# mapleSDuino-V0_1_016-eagle7.net
KiCad netlist of a schematic drawn in EAGLE
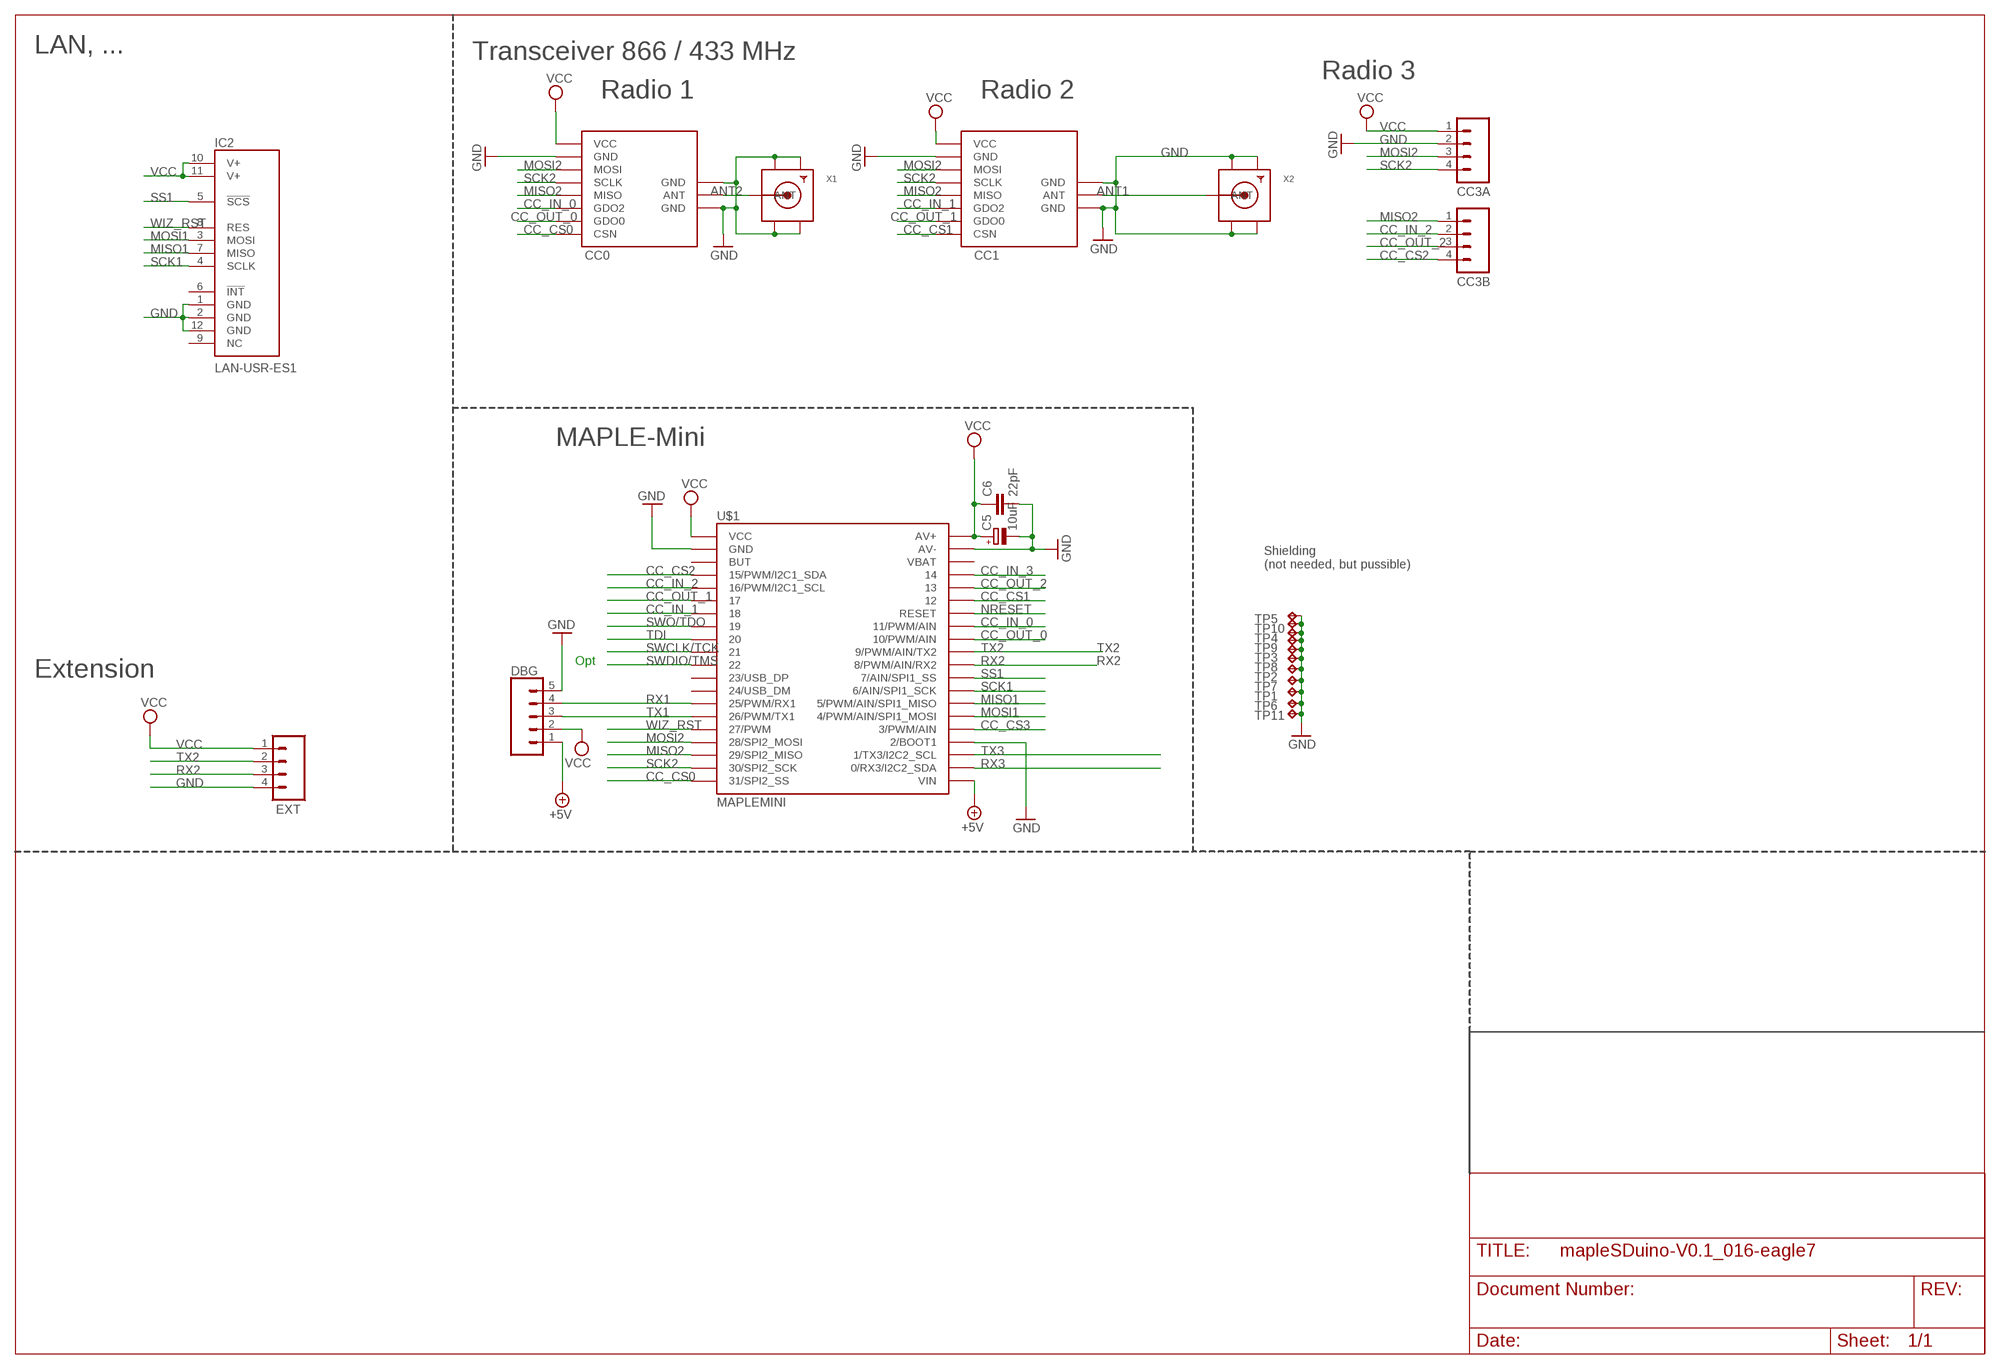
[diagram p0: schematic, sheet 1]

(export (version "E")
  (design (tool "Eeschema 10.0.6"))
  (components
    (comp (ref "C5")
      (value "10uF")
      (footprint "eagle-import:R_2012-12W")
      (libsource (lib "eagle-import") (part "CPOL-EUR/2012-12W"))
    )
    (comp (ref "C6")
      (value "22pF")
      (footprint "eagle-import:C0805")
      (libsource (lib "eagle-import") (part "C-EUC0805"))
    )
    (comp (ref "CC0")
      (value "CC1101")
      (footprint "eagle-import:CC1101_MODULE1_SMD")
      (libsource (lib "eagle-import") (part "CC1101_MODULE1SMD"))
    )
    (comp (ref "CC1")
      (value "CC1101_MODULE1SMD")
      (footprint "eagle-import:CC1101_MODULE1_SMD")
      (libsource (lib "eagle-import") (part "CC1101_MODULE1SMD"))
    )
    (comp (ref "CC3A")
      (value "CONN_04PTH")
      (footprint "eagle-import:1X04")
      (libsource (lib "eagle-import") (part "CONN_04PTH"))
    )
    (comp (ref "CC3B")
      (value "CONN_04PTH")
      (footprint "eagle-import:1X04")
      (libsource (lib "eagle-import") (part "CONN_04PTH"))
    )
    (comp (ref "DBG")
      (value "CONN_05LOCK")
      (footprint "eagle-import:1X05_LOCK")
      (libsource (lib "eagle-import") (part "CONN_05LOCK"))
    )
    (comp (ref "EXT")
      (value "CONN_04PTH")
      (footprint "eagle-import:1X04")
      (libsource (lib "eagle-import") (part "CONN_04PTH"))
    )
    (comp (ref "IC2")
      (value "LAN-USR-ES1")
      (footprint "eagle-import:USR-ES1")
      (libsource (lib "eagle-import") (part "LAN-USR-ES1"))
    )
    (comp (ref "TP1")
      (value "TPTP06SQ")
      (footprint "eagle-import:TP06SQ")
      (libsource (lib "eagle-import") (part "TPTP06SQ"))
    )
    (comp (ref "TP2")
      (value "TPTP06SQ")
      (footprint "eagle-import:TP06SQ")
      (libsource (lib "eagle-import") (part "TPTP06SQ"))
    )
    (comp (ref "TP3")
      (value "TPTP06SQ")
      (footprint "eagle-import:TP06SQ")
      (libsource (lib "eagle-import") (part "TPTP06SQ"))
    )
    (comp (ref "TP4")
      (value "TPTP06SQ")
      (footprint "eagle-import:TP06SQ")
      (libsource (lib "eagle-import") (part "TPTP06SQ"))
    )
    (comp (ref "TP5")
      (value "TPTP06SQ")
      (footprint "eagle-import:TP06SQ")
      (libsource (lib "eagle-import") (part "TPTP06SQ"))
    )
    (comp (ref "TP6")
      (value "TPTP06SQ")
      (footprint "eagle-import:TP06SQ")
      (libsource (lib "eagle-import") (part "TPTP06SQ"))
    )
    (comp (ref "TP7")
      (value "TPTP06SQ")
      (footprint "eagle-import:TP06SQ")
      (libsource (lib "eagle-import") (part "TPTP06SQ"))
    )
    (comp (ref "TP8")
      (value "TPTP06SQ")
      (footprint "eagle-import:TP06SQ")
      (libsource (lib "eagle-import") (part "TPTP06SQ"))
    )
    (comp (ref "TP9")
      (value "TPTP06SQ")
      (footprint "eagle-import:TP06SQ")
      (libsource (lib "eagle-import") (part "TPTP06SQ"))
    )
    (comp (ref "TP10")
      (value "TPTP06SQ")
      (footprint "eagle-import:TP06SQ")
      (libsource (lib "eagle-import") (part "TPTP06SQ"))
    )
    (comp (ref "TP11")
      (value "TPTP06SQ")
      (footprint "eagle-import:TP06SQ")
      (libsource (lib "eagle-import") (part "TPTP06SQ"))
    )
    (comp (ref "U$1")
      (value "MAPLEMINI")
      (footprint "eagle-import:20-DIP")
      (libsource (lib "eagle-import") (part "MAPLEMINI"))
    )
    (comp (ref "X1")
      (value "SMACONNECTOR_EDGE")
      (footprint "eagle-import:SMA_EDGELAUNCH")
      (libsource (lib "eagle-import") (part "SMACONNECTOR_EDGE"))
    )
    (comp (ref "X2")
      (value "SMACONNECTOR_EDGE")
      (footprint "eagle-import:SMA_EDGELAUNCH")
      (libsource (lib "eagle-import") (part "SMACONNECTOR_EDGE"))
    )
  )
  (nets
    (net (code "1") (name "+5V") (class "Default")
      (node (ref "DBG") (pin "1") (pinfunction "1_1") (pintype "passive"))
      (node (ref "U$1") (pin "21") (pinfunction "VIN_21") (pintype "bidirectional"))
    )
    (net (code "2") (name "/ANT1") (class "Default")
      (node (ref "CC1") (pin "ANT") (pinfunction "ANT_ANT") (pintype "output"))
      (node (ref "X2") (pin "P") (pinfunction "ANT_P") (pintype "bidirectional"))
    )
    (net (code "3") (name "/ANT2") (class "Default")
      (node (ref "CC0") (pin "ANT") (pinfunction "ANT_ANT") (pintype "output"))
      (node (ref "X1") (pin "P") (pinfunction "ANT_P") (pintype "bidirectional"))
    )
    (net (code "4") (name "/CC_CS0") (class "Default")
      (node (ref "CC0") (pin "CSN") (pinfunction "CSN_CSN") (pintype "bidirectional"))
      (node (ref "U$1") (pin "20") (pinfunction "31/SPI2_SS_20") (pintype "bidirectional"))
    )
    (net (code "5") (name "/CC_CS1") (class "Default")
      (node (ref "CC1") (pin "CSN") (pinfunction "CSN_CSN") (pintype "bidirectional"))
      (node (ref "U$1") (pin "35") (pinfunction "12_35") (pintype "bidirectional"))
    )
    (net (code "6") (name "/CC_CS2") (class "Default")
      (node (ref "CC3B") (pin "4") (pinfunction "4_4") (pintype "passive"))
      (node (ref "U$1") (pin "4") (pinfunction "15/PWM/I2C1_SDA_4") (pintype "bidirectional"))
    )
    (net (code "7") (name "/CC_CS3") (class "Default")
      (node (ref "U$1") (pin "25") (pinfunction "3/PWM/AIN_25") (pintype "bidirectional"))
    )
    (net (code "8") (name "/CC_IN_0") (class "Default")
      (node (ref "CC0") (pin "GDO2") (pinfunction "GDO2_GDO2") (pintype "bidirectional"))
      (node (ref "U$1") (pin "33") (pinfunction "11/PWM/AIN_33") (pintype "bidirectional"))
    )
    (net (code "9") (name "/CC_IN_1") (class "Default")
      (node (ref "CC1") (pin "GDO2") (pinfunction "GDO2_GDO2") (pintype "bidirectional"))
      (node (ref "U$1") (pin "7") (pinfunction "18_7") (pintype "bidirectional"))
    )
    (net (code "10") (name "/CC_IN_2") (class "Default")
      (node (ref "CC3B") (pin "2") (pinfunction "2_2") (pintype "passive"))
      (node (ref "U$1") (pin "5") (pinfunction "16/PWM/I2C1_SCL_5") (pintype "bidirectional"))
    )
    (net (code "11") (name "/CC_IN_3") (class "Default")
      (node (ref "U$1") (pin "37") (pinfunction "14_37") (pintype "bidirectional"))
    )
    (net (code "12") (name "/CC_OUT_0") (class "Default")
      (node (ref "CC0") (pin "GDO0") (pinfunction "GDO0_GDO0") (pintype "bidirectional"))
      (node (ref "U$1") (pin "32") (pinfunction "10/PWM/AIN_32") (pintype "bidirectional"))
    )
    (net (code "13") (name "/CC_OUT_1") (class "Default")
      (node (ref "CC1") (pin "GDO0") (pinfunction "GDO0_GDO0") (pintype "bidirectional"))
      (node (ref "U$1") (pin "6") (pinfunction "17_6") (pintype "bidirectional"))
    )
    (net (code "14") (name "/CC_OUT_2") (class "Default")
      (node (ref "CC3B") (pin "3") (pinfunction "3_3") (pintype "passive"))
      (node (ref "U$1") (pin "36") (pinfunction "13_36") (pintype "bidirectional"))
    )
    (net (code "15") (name "/MISO1") (class "Default")
      (node (ref "IC2") (pin "7") (pinfunction "MISO_7") (pintype "bidirectional"))
      (node (ref "U$1") (pin "27") (pinfunction "5/PWM/AIN/SPI1_MISO_27") (pintype "bidirectional"))
    )
    (net (code "16") (name "/MISO2") (class "Default")
      (node (ref "CC0") (pin "MISO") (pinfunction "MISO_MISO") (pintype "bidirectional"))
      (node (ref "CC1") (pin "MISO") (pinfunction "MISO_MISO") (pintype "bidirectional"))
      (node (ref "CC3B") (pin "1") (pinfunction "1_1") (pintype "passive"))
      (node (ref "U$1") (pin "18") (pinfunction "29/SPI2_MISO_18") (pintype "bidirectional"))
    )
    (net (code "17") (name "/MOSI1") (class "Default")
      (node (ref "IC2") (pin "3") (pinfunction "MOSI_3") (pintype "bidirectional"))
      (node (ref "U$1") (pin "26") (pinfunction "4/PWM/AIN/SPI1_MOSI_26") (pintype "bidirectional"))
    )
    (net (code "18") (name "/MOSI2") (class "Default")
      (node (ref "CC0") (pin "MOSI") (pinfunction "MOSI_MOSI") (pintype "bidirectional"))
      (node (ref "CC1") (pin "MOSI") (pinfunction "MOSI_MOSI") (pintype "bidirectional"))
      (node (ref "CC3A") (pin "3") (pinfunction "3_3") (pintype "passive"))
      (node (ref "U$1") (pin "17") (pinfunction "28/SPI2_MOSI_17") (pintype "bidirectional"))
    )
    (net (code "19") (name "/NRESET") (class "Default")
      (node (ref "U$1") (pin "34") (pinfunction "RESET_34") (pintype "bidirectional"))
    )
    (net (code "20") (name "/RX1") (class "Default")
      (node (ref "DBG") (pin "4") (pinfunction "4_4") (pintype "passive"))
      (node (ref "U$1") (pin "14") (pinfunction "25/PWM/RX1_14") (pintype "bidirectional"))
    )
    (net (code "21") (name "/RX2") (class "Default")
      (node (ref "EXT") (pin "3") (pinfunction "3_3") (pintype "passive"))
      (node (ref "U$1") (pin "30") (pinfunction "8/PWM/AIN/RX2_30") (pintype "bidirectional"))
    )
    (net (code "22") (name "/RX3") (class "Default")
      (node (ref "U$1") (pin "22") (pinfunction "0/RX3/I2C2_SDA_22") (pintype "bidirectional"))
    )
    (net (code "23") (name "/SCK1") (class "Default")
      (node (ref "IC2") (pin "4") (pinfunction "SCLK_4") (pintype "input"))
      (node (ref "U$1") (pin "28") (pinfunction "6/AIN/SPI1_SCK_28") (pintype "bidirectional"))
    )
    (net (code "24") (name "/SCK2") (class "Default")
      (node (ref "CC0") (pin "SCLK") (pinfunction "SCLK_SCLK") (pintype "bidirectional"))
      (node (ref "CC1") (pin "SCLK") (pinfunction "SCLK_SCLK") (pintype "bidirectional"))
      (node (ref "CC3A") (pin "4") (pinfunction "4_4") (pintype "passive"))
      (node (ref "U$1") (pin "19") (pinfunction "30/SPI2_SCK_19") (pintype "bidirectional"))
    )
    (net (code "25") (name "/SS1") (class "Default")
      (node (ref "IC2") (pin "5") (pinfunction "~{SCS}_5") (pintype "input"))
      (node (ref "U$1") (pin "29") (pinfunction "7/AIN/SPI1_SS_29") (pintype "bidirectional"))
    )
    (net (code "26") (name "/SWCLK{slash}TCK") (class "Default")
      (node (ref "U$1") (pin "10") (pinfunction "21_10") (pintype "bidirectional"))
    )
    (net (code "27") (name "/SWDIO{slash}TMS") (class "Default")
      (node (ref "U$1") (pin "11") (pinfunction "22_11") (pintype "bidirectional"))
    )
    (net (code "28") (name "/SWO{slash}TDO") (class "Default")
      (node (ref "U$1") (pin "8") (pinfunction "19_8") (pintype "bidirectional"))
    )
    (net (code "29") (name "/TDI") (class "Default")
      (node (ref "U$1") (pin "9") (pinfunction "20_9") (pintype "bidirectional"))
    )
    (net (code "30") (name "/TX1") (class "Default")
      (node (ref "DBG") (pin "3") (pinfunction "3_3") (pintype "passive"))
      (node (ref "U$1") (pin "15") (pinfunction "26/PWM/TX1_15") (pintype "bidirectional"))
    )
    (net (code "31") (name "/TX2") (class "Default")
      (node (ref "EXT") (pin "2") (pinfunction "2_2") (pintype "passive"))
      (node (ref "U$1") (pin "31") (pinfunction "9/PWM/AIN/TX2_31") (pintype "bidirectional"))
    )
    (net (code "32") (name "/TX3") (class "Default")
      (node (ref "U$1") (pin "23") (pinfunction "1/TX3/I2C2_SCL_23") (pintype "bidirectional"))
    )
    (net (code "33") (name "/WIZ_RST") (class "Default")
      (node (ref "IC2") (pin "8") (pinfunction "RES_8") (pintype "input"))
      (node (ref "U$1") (pin "16") (pinfunction "27/PWM_16") (pintype "bidirectional"))
    )
    (net (code "34") (name "GND") (class "Default")
      (node (ref "C5") (pin "-") (pinfunction "-_-") (pintype "passive"))
      (node (ref "C6") (pin "2") (pinfunction "2_2") (pintype "passive"))
      (node (ref "CC0") (pin "GND@0") (pinfunction "GND_GND@0") (pintype "power_in"))
      (node (ref "CC0") (pin "GND@1") (pinfunction "GND_GND@1") (pintype "power_in"))
      (node (ref "CC0") (pin "GND@2") (pinfunction "GND_GND@2") (pintype "power_in"))
      (node (ref "CC1") (pin "GND@0") (pinfunction "GND_GND@0") (pintype "power_in"))
      (node (ref "CC1") (pin "GND@1") (pinfunction "GND_GND@1") (pintype "power_in"))
      (node (ref "CC1") (pin "GND@2") (pinfunction "GND_GND@2") (pintype "power_in"))
      (node (ref "CC3A") (pin "2") (pinfunction "2_2") (pintype "passive"))
      (node (ref "DBG") (pin "5") (pinfunction "5_5") (pintype "passive"))
      (node (ref "EXT") (pin "4") (pinfunction "4_4") (pintype "passive"))
      (node (ref "IC2") (pin "1") (pinfunction "GND_1") (pintype "power_in"))
      (node (ref "IC2") (pin "12") (pinfunction "GND_12") (pintype "power_in"))
      (node (ref "IC2") (pin "2") (pinfunction "GND_2") (pintype "power_in"))
      (node (ref "TP1") (pin "TP") (pinfunction "TP_TP") (pintype "input"))
      (node (ref "TP10") (pin "TP") (pinfunction "TP_TP") (pintype "input"))
      (node (ref "TP11") (pin "TP") (pinfunction "TP_TP") (pintype "input"))
      (node (ref "TP2") (pin "TP") (pinfunction "TP_TP") (pintype "input"))
      (node (ref "TP3") (pin "TP") (pinfunction "TP_TP") (pintype "input"))
      (node (ref "TP4") (pin "TP") (pinfunction "TP_TP") (pintype "input"))
      (node (ref "TP5") (pin "TP") (pinfunction "TP_TP") (pintype "input"))
      (node (ref "TP6") (pin "TP") (pinfunction "TP_TP") (pintype "input"))
      (node (ref "TP7") (pin "TP") (pinfunction "TP_TP") (pintype "input"))
      (node (ref "TP8") (pin "TP") (pinfunction "TP_TP") (pintype "input"))
      (node (ref "TP9") (pin "TP") (pinfunction "TP_TP") (pintype "input"))
      (node (ref "U$1") (pin "2") (pinfunction "GND_2") (pintype "bidirectional"))
      (node (ref "U$1") (pin "24") (pinfunction "2/BOOT1_24") (pintype "bidirectional"))
      (node (ref "U$1") (pin "39") (pinfunction "AV-_39") (pintype "bidirectional"))
      (node (ref "X1") (pin "GND@1") (pinfunction "GND4_GND@1") (pintype "power_in"))
      (node (ref "X1") (pin "GND@2") (pinfunction "GND3_GND@2") (pintype "power_in"))
      (node (ref "X1") (pin "GND@3") (pinfunction "GND2_GND@3") (pintype "power_in"))
      (node (ref "X1") (pin "GND@4") (pinfunction "GND1_GND@4") (pintype "power_in"))
      (node (ref "X2") (pin "GND@1") (pinfunction "GND4_GND@1") (pintype "power_in"))
      (node (ref "X2") (pin "GND@2") (pinfunction "GND3_GND@2") (pintype "power_in"))
      (node (ref "X2") (pin "GND@3") (pinfunction "GND2_GND@3") (pintype "power_in"))
      (node (ref "X2") (pin "GND@4") (pinfunction "GND1_GND@4") (pintype "power_in"))
    )
    (net (code "35") (name "VCC") (class "Default")
      (node (ref "C5") (pin "+") (pinfunction "+_+") (pintype "passive"))
      (node (ref "C6") (pin "1") (pinfunction "1_1") (pintype "passive"))
      (node (ref "CC0") (pin "VCC") (pinfunction "VCC_VCC") (pintype "power_in"))
      (node (ref "CC1") (pin "VCC") (pinfunction "VCC_VCC") (pintype "power_in"))
      (node (ref "CC3A") (pin "1") (pinfunction "1_1") (pintype "passive"))
      (node (ref "DBG") (pin "2") (pinfunction "2_2") (pintype "passive"))
      (node (ref "EXT") (pin "1") (pinfunction "1_1") (pintype "passive"))
      (node (ref "IC2") (pin "10") (pinfunction "V+_10") (pintype "power_in"))
      (node (ref "IC2") (pin "11") (pinfunction "V+_11") (pintype "power_in"))
      (node (ref "U$1") (pin "1") (pinfunction "VCC_1") (pintype "bidirectional"))
      (node (ref "U$1") (pin "40") (pinfunction "AV+_40") (pintype "bidirectional"))
    )
    (net (code "36") (name "unconnected-(IC2-NC-Pad9)") (class "Default")
      (node (ref "IC2") (pin "9") (pinfunction "NC_9") (pintype "no_connect"))
    )
    (net (code "37") (name "unconnected-(IC2-~{INT}-Pad6)") (class "Default")
      (node (ref "IC2") (pin "6") (pinfunction "~{INT}_6") (pintype "output"))
    )
    (net (code "38") (name "unconnected-(U$1-23{slash}USB_DP-Pad12)") (class "Default")
      (node (ref "U$1") (pin "12") (pinfunction "23/USB_DP_12") (pintype "bidirectional"))
    )
    (net (code "39") (name "unconnected-(U$1-24{slash}USB_DM-Pad13)") (class "Default")
      (node (ref "U$1") (pin "13") (pinfunction "24/USB_DM_13") (pintype "bidirectional"))
    )
    (net (code "40") (name "unconnected-(U$1-BUT-Pad3)") (class "Default")
      (node (ref "U$1") (pin "3") (pinfunction "BUT_3") (pintype "bidirectional"))
    )
    (net (code "41") (name "unconnected-(U$1-VBAT-Pad38)") (class "Default")
      (node (ref "U$1") (pin "38") (pinfunction "VBAT_38") (pintype "bidirectional"))
    )
  )
)
